# modFOC-Sensing.net
KiCad netlist of a schematic drawn in Altium Designer
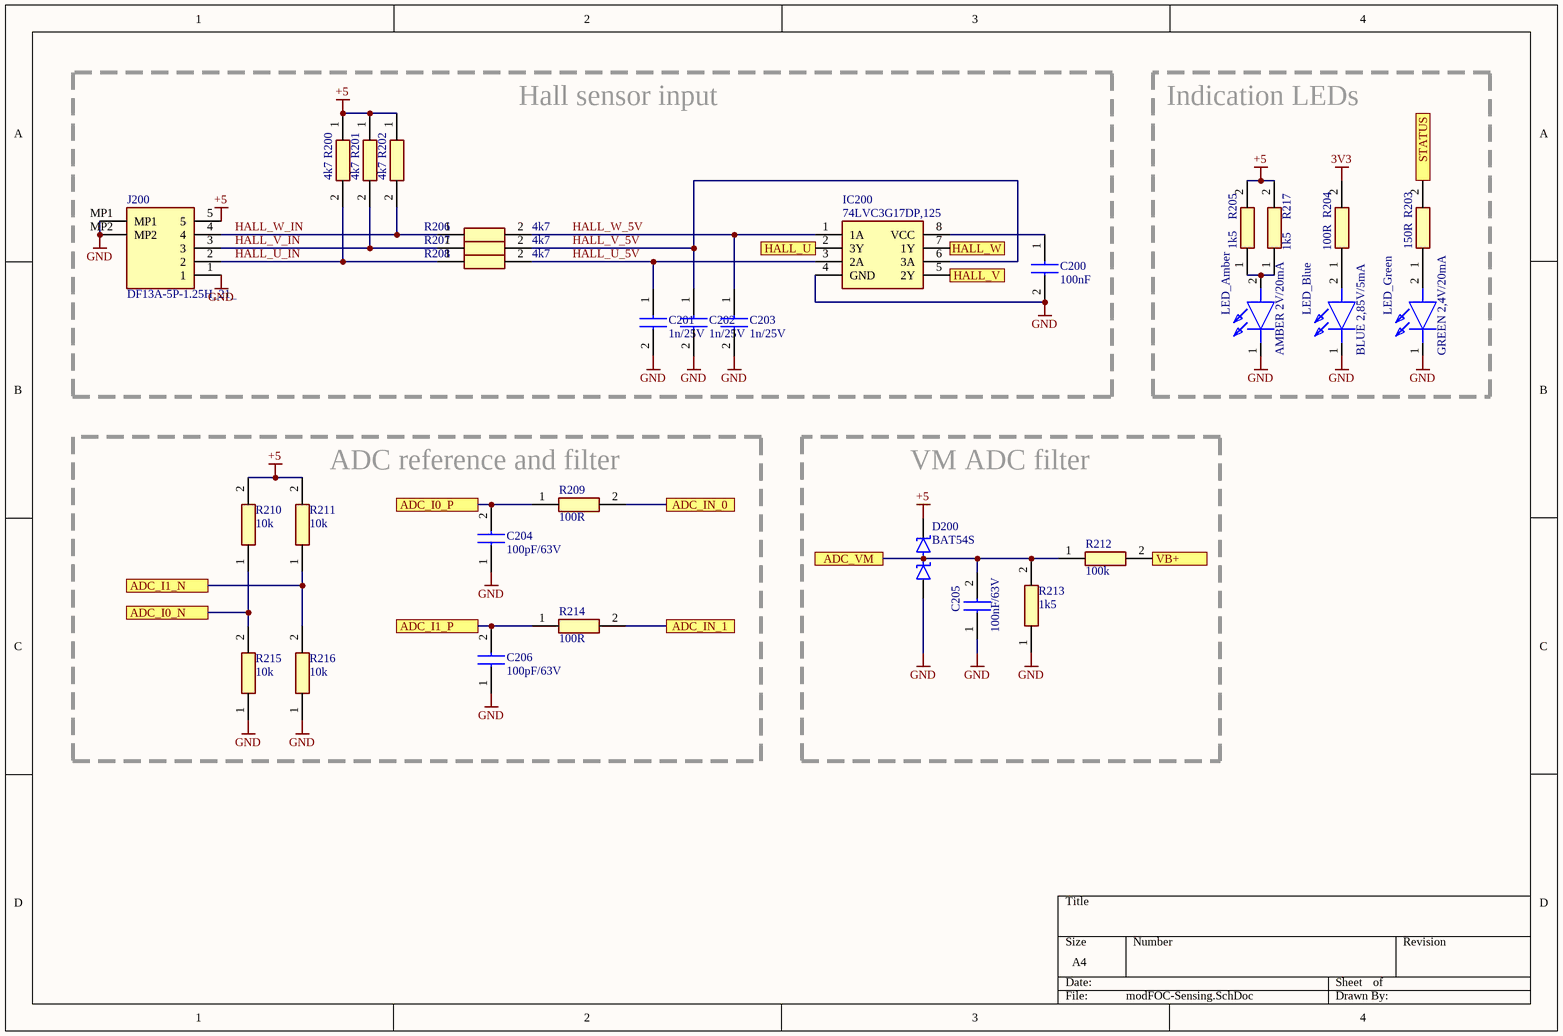
[diagram p0: modFOC-Sensing.SchDoc]

(export (version "E")
  (design (tool "Eeschema 10.0.6"))
  (components
    (comp (ref "C200")
      (value "100nF")
      (footprint "PcbLib1:CAPC1608X97N")
      (description "Capacitor")
      (fields
        (field (name "MANUFACTURER_PART_NUMBER") "VJ0603Y104JXJAC")
        (field (name "MOUSER PART NUMBER") "77-VJ0603Y104JXJAC")
      )
      (libsource (lib "Schlib1") (part "VJ0603Y104JXJAC"))
    )
    (comp (ref "C201")
      (value "1n/25V")
      (footprint "PcbLib1:CAPC1608X97N")
      (description "Capacitor")
      (fields
        (field (name "MANUFACTURER_PART_NUMBER") "GRM033R71E102KA01D")
        (field (name "MOUSER PART NUMBER") "81-GRM033R71E102KA1D")
      )
      (libsource (lib "Schlib1") (part "GRM033R71E102KA01D"))
    )
    (comp (ref "C202")
      (value "1n/25V")
      (footprint "PcbLib1:CAPC1608X97N")
      (description "Capacitor")
      (fields
        (field (name "MANUFACTURER_PART_NUMBER") "GRM033R71E102KA01D")
        (field (name "MOUSER PART NUMBER") "81-GRM033R71E102KA1D")
      )
      (libsource (lib "Schlib1") (part "GRM033R71E102KA01D"))
    )
    (comp (ref "C203")
      (value "1n/25V")
      (footprint "PcbLib1:CAPC1608X97N")
      (description "Capacitor")
      (fields
        (field (name "MANUFACTURER_PART_NUMBER") "GRM033R71E102KA01D")
        (field (name "MOUSER PART NUMBER") "81-GRM033R71E102KA1D")
      )
      (libsource (lib "Schlib1") (part "GRM033R71E102KA01D"))
    )
    (comp (ref "C204")
      (value "100pF/63V")
      (footprint "PcbLib1:CAPC1608X87N")
      (description "Capacitor")
      (fields
        (field (name "MANUFACTURER_PART_NUMBER") "C0603C101K1HACTU")
        (field (name "MOUSER PART NUMBER") "80-C0603C101K1HACTU")
      )
      (libsource (lib "Schlib1") (part "C0603C101K1HACTU"))
    )
    (comp (ref "C205")
      (value "100nF/63V")
      (footprint "PcbLib1:CAPC1608X97N")
      (description "Capacitor")
      (fields
        (field (name "MANUFACTURER_PART_NUMBER") "VJ0603Y104JXJAC")
        (field (name "MOUSER PART NUMBER") "77-VJ0603Y104JXJAC")
      )
      (libsource (lib "Schlib1") (part "C0805C104MMREC7210"))
    )
    (comp (ref "C206")
      (value "100pF/63V")
      (footprint "PcbLib1:CAPC1608X87N")
      (description "Capacitor")
      (fields
        (field (name "MANUFACTURER_PART_NUMBER") "C0603C101K1HACTU")
        (field (name "MOUSER PART NUMBER") "80-C0603C101K1HACTU")
      )
      (libsource (lib "Schlib1") (part "C0603C101K1HACTU"))
    )
    (comp (ref "D200")
      (value "BAT54S")
      (footprint "PcbLib1:SOT95P240X110-3N")
      (description "Schottky Diode")
      (fields (field (name "MOUSER PART NUMBER") "583-BAT54S"))
      (libsource (lib "Schlib1") (part "BAT54S"))
    )
    (comp (ref "IC200")
      (value "74LVC3G17DP,125")
      (footprint "PcbLib1:SOP65P400X110-8N")
      (description "Integrated Circuit")
      (fields (field (name "MOUSER PART NUMBER") "771-LVC3G17DP125"))
      (libsource (lib "*") (part "74LVC3G17DP,125"))
    )
    (comp (ref "J200")
      (value "DF13A-5P-1.25H_21_")
      (footprint "PcbLib1:DF13A5P125H21")
      (description "Connector")
      (fields
        (field (name "MANUFACTURER_PART_NUMBER") "DF13A-5P-1.25H(21)")
        (field (name "MOUSER PART NUMBER") "798-DF13A5P125H21")
      )
      (libsource (lib "Schlib1") (part "DF13A-5P-1.25H_21_"))
    )
    (comp (ref "LED_Amber")
      (value "AMBER 2V/20mA")
      (footprint "PcbLib1:LEDC1608X55N")
      (description "LED")
      (fields
        (field (name "MANUFACTURER_PART_NUMBER") "ASMT-RA45-AP932")
        (field (name "MOUSER PART NUMBER") "630-ASMT-RA45-AP932")
      )
      (libsource (lib "*") (part "ASMT-RA45-AP932"))
    )
    (comp (ref "LED_Blue")
      (value "BLUE 2,85V/5mA")
      (footprint "PcbLib1:LEDC1608X40N")
      (description "LED")
      (fields
        (field (name "MANUFACTURER_PART_NUMBER") "LB Q39G-L2OO-35-1")
        (field (name "MOUSER PART NUMBER") "720-LBQ39GL2N2351")
      )
      (libsource (lib "*") (part "LB_Q39G-L2OO-35-1"))
    )
    (comp (ref "LED_Green")
      (value "GREEN 2,4V/20mA")
      (footprint "PcbLib1:LGQ396PS35")
      (description "LED")
      (fields
        (field (name "MANUFACTURER_PART_NUMBER") "LG Q396-PS-35")
        (field (name "MOUSER PART NUMBER") "720-LGQ396A3964")
      )
      (libsource (lib "*") (part "LG_Q396-PS-35"))
    )
    (comp (ref "R200")
      (value "4k7")
      (footprint "PcbLib1:RESC1608X55N")
      (description "Resistor")
      (fields
        (field (name "MANUFACTURER_PART_NUMBER") "CRCW06034K70JNEAC")
        (field (name "MOUSER PART NUMBER") "71-CRCW06034K70JNEAC")
      )
      (libsource (lib "") (part "CRCW06034K70JNEAC_1"))
    )
    (comp (ref "R201")
      (value "4k7")
      (footprint "PcbLib1:RESC1608X55N")
      (description "Resistor")
      (fields
        (field (name "MANUFACTURER_PART_NUMBER") "CRCW06034K70JNEAC")
        (field (name "MOUSER PART NUMBER") "71-CRCW06034K70JNEAC")
      )
      (libsource (lib "") (part "CRCW06034K70JNEAC_1"))
    )
    (comp (ref "R202")
      (value "4k7")
      (footprint "PcbLib1:RESC1608X55N")
      (description "Resistor")
      (fields
        (field (name "MANUFACTURER_PART_NUMBER") "CRCW06034K70JNEAC")
        (field (name "MOUSER PART NUMBER") "71-CRCW06034K70JNEAC")
      )
      (libsource (lib "") (part "CRCW06034K70JNEAC_1"))
    )
    (comp (ref "R203")
      (value "150R")
      (footprint "PcbLib1:RESC1608X55N")
      (description "Resistor")
      (fields
        (field (name "MANUFACTURER_PART_NUMBER") "SFR03EZPF1500")
        (field (name "MOUSER PART NUMBER") "755-SFR03EZPF1500")
      )
      (libsource (lib "*") (part "SFR03EZPF1500"))
    )
    (comp (ref "R204")
      (value "100R")
      (footprint "PcbLib1:RESC1608X55N")
      (description "Resistor")
      (fields
        (field (name "MANUFACTURER_PART_NUMBER") "CRCW0603100RFKEAC")
        (field (name "MOUSER PART NUMBER") "71-CRCW0603100RFKEAC")
      )
      (libsource (lib "") (part "CRCW0603100RFKEAC_1"))
    )
    (comp (ref "R205")
      (value "1k5")
      (footprint "PcbLib1:RESC1608X55N")
      (description "Resistor")
      (fields (field (name "MANUFACTURER_PART_NUMBER") "ERJ1GNF1501C"))
      (libsource (lib "Schlib1") (part "ERJ1GNF1501C"))
    )
    (comp (ref "R206")
      (value "4k7")
      (footprint "PcbLib1:RESC1608X55N")
      (description "Resistor")
      (fields
        (field (name "MANUFACTURER_PART_NUMBER") "CRCW06034K70JNEAC")
        (field (name "MOUSER PART NUMBER") "71-CRCW06034K70JNEAC")
      )
      (libsource (lib "*") (part "CRCW06034K70JNEAC"))
    )
    (comp (ref "R207")
      (value "4k7")
      (footprint "PcbLib1:RESC1608X55N")
      (description "Resistor")
      (fields
        (field (name "MANUFACTURER_PART_NUMBER") "CRCW06034K70JNEAC")
        (field (name "MOUSER PART NUMBER") "71-CRCW06034K70JNEAC")
      )
      (libsource (lib "*") (part "CRCW06034K70JNEAC"))
    )
    (comp (ref "R208")
      (value "4k7")
      (footprint "PcbLib1:RESC1608X55N")
      (description "Resistor")
      (fields
        (field (name "MANUFACTURER_PART_NUMBER") "CRCW06034K70JNEAC")
        (field (name "MOUSER PART NUMBER") "71-CRCW06034K70JNEAC")
      )
      (libsource (lib "*") (part "CRCW06034K70JNEAC"))
    )
    (comp (ref "R209")
      (value "100R")
      (footprint "PcbLib1:RESC1608X55N")
      (description "Resistor")
      (fields
        (field (name "MANUFACTURER_PART_NUMBER") "CRCW0603100RFKEAC")
        (field (name "MOUSER PART NUMBER") "71-CRCW0603100RFKEAC")
      )
      (libsource (lib "*") (part "CRCW0603100RFKEAC"))
    )
    (comp (ref "R210")
      (value "10k")
      (footprint "PcbLib1:RESC1608X55N")
      (description "Resistor")
      (fields
        (field (name "MANUFACTURER_PART_NUMBER") "RC0603FR-0710KL")
        (field (name "MOUSER PART NUMBER") "603-RC0603FR-0710KL")
      )
      (libsource (lib "*") (part "RC0603FR-0710KL"))
    )
    (comp (ref "R211")
      (value "10k")
      (footprint "PcbLib1:RESC1608X55N")
      (description "Resistor")
      (fields
        (field (name "MANUFACTURER_PART_NUMBER") "RC0603FR-0710KL")
        (field (name "MOUSER PART NUMBER") "603-RC0603FR-0710KL")
      )
      (libsource (lib "*") (part "RC0603FR-0710KL"))
    )
    (comp (ref "R212")
      (value "100k")
      (footprint "PcbLib1:RESC1608X55N")
      (description "Resistor")
      (fields (field (name "MANUFACTURER_PART_NUMBER") "ERJ1GNF1003C"))
      (libsource (lib "Schlib1") (part "ERJ1GNF1003C"))
    )
    (comp (ref "R213")
      (value "1k5")
      (footprint "PcbLib1:RESC1608X55N")
      (description "Resistor")
      (fields (field (name "MANUFACTURER_PART_NUMBER") "ERJ1GNF1501C"))
      (libsource (lib "Schlib1") (part "ERJ1GNF1501C"))
    )
    (comp (ref "R214")
      (value "100R")
      (footprint "PcbLib1:RESC1608X55N")
      (description "Resistor")
      (fields
        (field (name "MANUFACTURER_PART_NUMBER") "CRCW0603100RFKEAC")
        (field (name "MOUSER PART NUMBER") "71-CRCW0603100RFKEAC")
      )
      (libsource (lib "*") (part "CRCW0603100RFKEAC"))
    )
    (comp (ref "R215")
      (value "10k")
      (footprint "PcbLib1:RESC1608X55N")
      (description "Resistor")
      (fields
        (field (name "MANUFACTURER_PART_NUMBER") "RC0603FR-0710KL")
        (field (name "MOUSER PART NUMBER") "603-RC0603FR-0710KL")
      )
      (libsource (lib "*") (part "RC0603FR-0710KL"))
    )
    (comp (ref "R216")
      (value "10k")
      (footprint "PcbLib1:RESC1608X55N")
      (description "Resistor")
      (fields
        (field (name "MANUFACTURER_PART_NUMBER") "RC0603FR-0710KL")
        (field (name "MOUSER PART NUMBER") "603-RC0603FR-0710KL")
      )
      (libsource (lib "*") (part "RC0603FR-0710KL"))
    )
    (comp (ref "R217")
      (value "1k5")
      (footprint "PcbLib1:RESC1608X55N")
      (description "Resistor")
      (fields (field (name "MANUFACTURER_PART_NUMBER") "ERJ1GNF1501C"))
      (libsource (lib "Schlib1") (part "ERJ1GNF1501C"))
    )
  )
  (nets
    (net (code "1") (name "+5") (class "Default")
      (node (ref "D200") (pin "2") (pinfunction "K_2") (pintype "passive"))
      (node (ref "J200") (pin "5") (pinfunction "5_5") (pintype "passive"))
      (node (ref "R200") (pin "1") (pinfunction "1_1") (pintype "passive"))
      (node (ref "R201") (pin "1") (pinfunction "1_1") (pintype "passive"))
      (node (ref "R202") (pin "1") (pinfunction "1_1") (pintype "passive"))
      (node (ref "R205") (pin "2") (pinfunction "2_2") (pintype "passive"))
      (node (ref "R210") (pin "2") (pinfunction "2_2") (pintype "passive"))
      (node (ref "R211") (pin "2") (pinfunction "2_2") (pintype "passive"))
      (node (ref "R217") (pin "2") (pinfunction "2_2") (pintype "passive"))
    )
    (net (code "2") (name "/ADC_I0_N") (class "Default")
      (node (ref "R210") (pin "1") (pinfunction "1_1") (pintype "passive"))
      (node (ref "R215") (pin "2") (pinfunction "2_2") (pintype "passive"))
    )
    (net (code "3") (name "/ADC_I0_P") (class "Default")
      (node (ref "C204") (pin "2") (pinfunction "2_2") (pintype "passive"))
      (node (ref "R209") (pin "1") (pinfunction "1_1") (pintype "passive"))
    )
    (net (code "4") (name "/ADC_I1_N") (class "Default")
      (node (ref "R211") (pin "1") (pinfunction "1_1") (pintype "passive"))
      (node (ref "R216") (pin "2") (pinfunction "2_2") (pintype "passive"))
    )
    (net (code "5") (name "/ADC_I1_P") (class "Default")
      (node (ref "C206") (pin "2") (pinfunction "2_2") (pintype "passive"))
      (node (ref "R214") (pin "1") (pinfunction "1_1") (pintype "passive"))
    )
    (net (code "6") (name "/ADC_IN_0") (class "Default")
      (node (ref "R209") (pin "2") (pinfunction "2_2") (pintype "passive"))
    )
    (net (code "7") (name "/ADC_IN_1") (class "Default")
      (node (ref "R214") (pin "2") (pinfunction "2_2") (pintype "passive"))
    )
    (net (code "8") (name "/ADC_VM") (class "Default")
      (node (ref "C205") (pin "2") (pinfunction "2_2") (pintype "passive"))
      (node (ref "D200") (pin "3") (pinfunction "A/K_3") (pintype "passive"))
      (node (ref "R212") (pin "1") (pinfunction "1_1") (pintype "passive"))
      (node (ref "R213") (pin "2") (pinfunction "2_2") (pintype "passive"))
    )
    (net (code "9") (name "/HALL_U") (class "Default")
      (node (ref "IC200") (pin "2") (pinfunction "3Y_2") (pintype "passive"))
    )
    (net (code "10") (name "/HALL_U_5V") (class "Default")
      (node (ref "C201") (pin "1") (pinfunction "1_1") (pintype "passive"))
      (node (ref "IC200") (pin "3") (pinfunction "2A_3") (pintype "passive"))
      (node (ref "R208") (pin "2") (pinfunction "2_2") (pintype "passive"))
    )
    (net (code "11") (name "/HALL_U_IN") (class "Default")
      (node (ref "J200") (pin "2") (pinfunction "2_2") (pintype "passive"))
      (node (ref "R200") (pin "2") (pinfunction "2_2") (pintype "passive"))
      (node (ref "R208") (pin "1") (pinfunction "1_1") (pintype "passive"))
    )
    (net (code "12") (name "/HALL_V") (class "Default")
      (node (ref "IC200") (pin "5") (pinfunction "2Y_5") (pintype "passive"))
    )
    (net (code "13") (name "/HALL_V_5V") (class "Default")
      (node (ref "C202") (pin "1") (pinfunction "1_1") (pintype "passive"))
      (node (ref "IC200") (pin "6") (pinfunction "3A_6") (pintype "passive"))
      (node (ref "R207") (pin "2") (pinfunction "2_2") (pintype "passive"))
    )
    (net (code "14") (name "/HALL_V_IN") (class "Default")
      (node (ref "J200") (pin "3") (pinfunction "3_3") (pintype "passive"))
      (node (ref "R201") (pin "2") (pinfunction "2_2") (pintype "passive"))
      (node (ref "R207") (pin "1") (pinfunction "1_1") (pintype "passive"))
    )
    (net (code "15") (name "/HALL_W") (class "Default")
      (node (ref "IC200") (pin "7") (pinfunction "1Y_7") (pintype "passive"))
    )
    (net (code "16") (name "/HALL_W_5V") (class "Default")
      (node (ref "C203") (pin "1") (pinfunction "1_1") (pintype "passive"))
      (node (ref "IC200") (pin "1") (pinfunction "1A_1") (pintype "passive"))
      (node (ref "R206") (pin "2") (pinfunction "2_2") (pintype "passive"))
    )
    (net (code "17") (name "/HALL_W_IN") (class "Default")
      (node (ref "J200") (pin "4") (pinfunction "4_4") (pintype "passive"))
      (node (ref "R202") (pin "2") (pinfunction "2_2") (pintype "passive"))
      (node (ref "R206") (pin "1") (pinfunction "1_1") (pintype "passive"))
    )
    (net (code "18") (name "/STATUS") (class "Default")
      (node (ref "R203") (pin "2") (pinfunction "2_2") (pintype "passive"))
    )
    (net (code "19") (name "/VB+") (class "Default")
      (node (ref "R212") (pin "2") (pinfunction "2_2") (pintype "passive"))
    )
    (net (code "20") (name "3V3") (class "Default")
      (node (ref "R204") (pin "2") (pinfunction "2_2") (pintype "passive"))
    )
    (net (code "21") (name "GND") (class "Default")
      (node (ref "C200") (pin "2") (pinfunction "2_2") (pintype "passive"))
      (node (ref "C201") (pin "2") (pinfunction "2_2") (pintype "passive"))
      (node (ref "C202") (pin "2") (pinfunction "2_2") (pintype "passive"))
      (node (ref "C203") (pin "2") (pinfunction "2_2") (pintype "passive"))
      (node (ref "C204") (pin "1") (pinfunction "1_1") (pintype "passive"))
      (node (ref "C205") (pin "1") (pinfunction "1_1") (pintype "passive"))
      (node (ref "C206") (pin "1") (pinfunction "1_1") (pintype "passive"))
      (node (ref "D200") (pin "1") (pinfunction "A_1") (pintype "passive"))
      (node (ref "IC200") (pin "4") (pinfunction "GND_4") (pintype "passive"))
      (node (ref "J200") (pin "1") (pinfunction "1_1") (pintype "passive"))
      (node (ref "J200") (pin "MP1") (pinfunction "MP1_MP1") (pintype "passive"))
      (node (ref "J200") (pin "MP2") (pinfunction "MP2_MP2") (pintype "passive"))
      (node (ref "LED_Amber") (pin "1") (pinfunction "K_1") (pintype "passive"))
      (node (ref "LED_Blue") (pin "1") (pinfunction "K_1") (pintype "passive"))
      (node (ref "LED_Green") (pin "1") (pinfunction "K_1") (pintype "passive"))
      (node (ref "R213") (pin "1") (pinfunction "1_1") (pintype "passive"))
      (node (ref "R215") (pin "1") (pinfunction "1_1") (pintype "passive"))
      (node (ref "R216") (pin "1") (pinfunction "1_1") (pintype "passive"))
    )
    (net (code "22") (name "Net-(IC200-VCC)") (class "Default")
      (node (ref "C200") (pin "1") (pinfunction "1_1") (pintype "passive"))
      (node (ref "IC200") (pin "8") (pinfunction "VCC_8") (pintype "passive"))
    )
    (net (code "23") (name "Net-(LED_Amber-A)") (class "Default")
      (node (ref "LED_Amber") (pin "2") (pinfunction "A_2") (pintype "passive"))
      (node (ref "R205") (pin "1") (pinfunction "1_1") (pintype "passive"))
      (node (ref "R217") (pin "1") (pinfunction "1_1") (pintype "passive"))
    )
    (net (code "24") (name "Net-(LED_Blue-A)") (class "Default")
      (node (ref "LED_Blue") (pin "2") (pinfunction "A_2") (pintype "passive"))
      (node (ref "R204") (pin "1") (pinfunction "1_1") (pintype "passive"))
    )
    (net (code "25") (name "Net-(LED_Green-A)") (class "Default")
      (node (ref "LED_Green") (pin "2") (pinfunction "A_2") (pintype "passive"))
      (node (ref "R203") (pin "1") (pinfunction "1_1") (pintype "passive"))
    )
  )
)
